# Arturo_Eagle_7_X.net
KiCad netlist of a schematic drawn in EAGLE
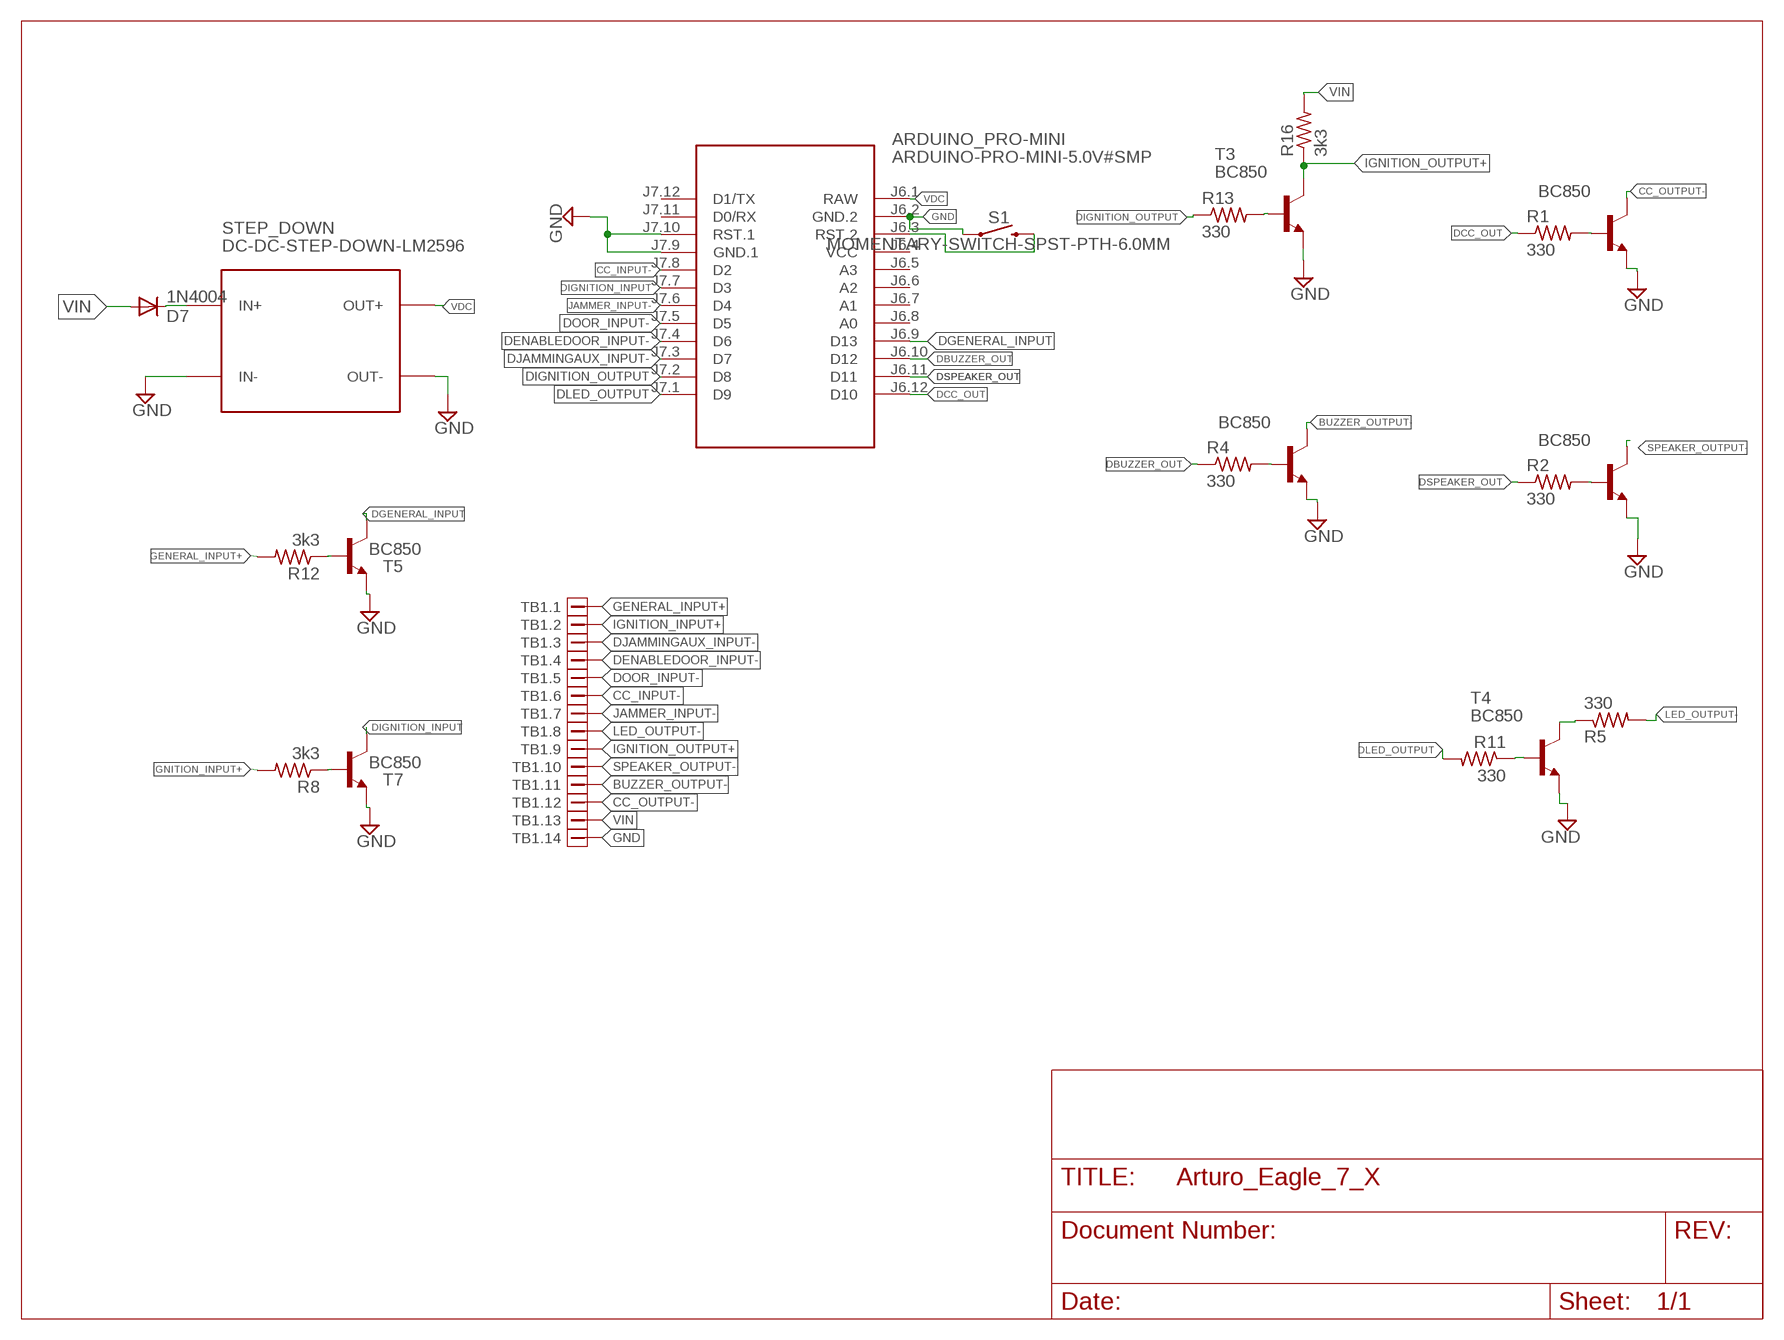
[diagram p0: schematic, sheet 1]

(export (version "E")
  (design (tool "Eeschema 10.0.6"))
  (components
    (comp (ref "ARDUINO_PRO-MINI")
      (value "ARDUINO-PRO-MINI-5.0V#SMP")
      (footprint "eagle-import:ARDUINO-PRO-MINI#SMP")
      (libsource (lib "eagle-import") (part "ARDUINO-PRO-MINI-#SMP5.0V"))
    )
    (comp (ref "D7")
      (value "1N4004")
      (footprint "eagle-import:DO41-10")
      (libsource (lib "eagle-import") (part "1N4004"))
    )
    (comp (ref "R1")
      (value "330")
      (footprint "eagle-import:R0805")
      (libsource (lib "eagle-import") (part "R-US_R0805"))
    )
    (comp (ref "R2")
      (value "330")
      (footprint "eagle-import:R0805")
      (libsource (lib "eagle-import") (part "R-US_R0805"))
    )
    (comp (ref "R4")
      (value "330")
      (footprint "eagle-import:R0805")
      (libsource (lib "eagle-import") (part "R-US_R0805"))
    )
    (comp (ref "R5")
      (value "330")
      (footprint "eagle-import:R0805")
      (libsource (lib "eagle-import") (part "R-US_R0805"))
    )
    (comp (ref "R8")
      (value "3k3")
      (footprint "eagle-import:R0805")
      (libsource (lib "eagle-import") (part "R-US_R0805"))
    )
    (comp (ref "R11")
      (value "330")
      (footprint "eagle-import:R0805")
      (libsource (lib "eagle-import") (part "R-US_R0805"))
    )
    (comp (ref "R12")
      (value "3k3")
      (footprint "eagle-import:R0805")
      (libsource (lib "eagle-import") (part "R-US_R0805"))
    )
    (comp (ref "R13")
      (value "330")
      (footprint "eagle-import:R0805")
      (libsource (lib "eagle-import") (part "R-US_R0805"))
    )
    (comp (ref "R16")
      (value "3k3")
      (footprint "eagle-import:R0805")
      (libsource (lib "eagle-import") (part "R-US_R0805"))
    )
    (comp (ref "S1")
      (value "MOMENTARY-SWITCH-SPST-PTH-6.0MM")
      (footprint "eagle-import:TACTILE_SWITCH_PTH_6.0MM")
      (libsource (lib "eagle-import") (part "MOMENTARY-SWITCH-SPST-PTH-6.0MM"))
    )
    (comp (ref "STEP_DOWN")
      (value "DC-DC-STEP-DOWN-LM2596")
      (footprint "eagle-import:DC-DC-STEP-DOWN-LM2596")
      (libsource (lib "eagle-import") (part "DC-DC-STEP-DOWN-LM2596"))
    )
    (comp (ref "T1")
      (value "BC850")
      (footprint "eagle-import:SOT23")
      (libsource (lib "eagle-import") (part "BC850"))
    )
    (comp (ref "T3")
      (value "BC850")
      (footprint "eagle-import:SOT23")
      (libsource (lib "eagle-import") (part "BC850"))
    )
    (comp (ref "T4")
      (value "BC850")
      (footprint "eagle-import:SOT23")
      (libsource (lib "eagle-import") (part "BC850"))
    )
    (comp (ref "T5")
      (value "BC850")
      (footprint "eagle-import:SOT23")
      (libsource (lib "eagle-import") (part "BC850"))
    )
    (comp (ref "T6")
      (value "BC850")
      (footprint "eagle-import:SOT23")
      (libsource (lib "eagle-import") (part "BC850"))
    )
    (comp (ref "T7")
      (value "BC850")
      (footprint "eagle-import:SOT23")
      (libsource (lib "eagle-import") (part "BC850"))
    )
    (comp (ref "T8")
      (value "BC850")
      (footprint "eagle-import:SOT23")
      (libsource (lib "eagle-import") (part "BC850"))
    )
    (comp (ref "TB1")
      (value "TB_PHOENIX")
      (footprint "eagle-import:TERMINAL_BLOCK_14POS")
      (libsource (lib "eagle-import") (part "TB_PHOENIX"))
    )
  )
  (nets
    (net (code "1") (name "/VCC") (class "Default")
      (node (ref "ARDUINO_PRO-MINI") (pin "J6.4") (pinfunction "VCC_J6.4") (pintype "power_in"))
    )
    (net (code "2") (name "BUZZER_OUTPUT-") (class "Default")
      (node (ref "T6") (pin "3") (pinfunction "C_3") (pintype "passive"))
      (node (ref "TB1") (pin "11") (pinfunction "1_11") (pintype "passive"))
      (node (ref "TB1") (pin "25") (pinfunction "1_25") (pintype "passive"))
    )
    (net (code "3") (name "CC_INPUT-") (class "Default")
      (node (ref "ARDUINO_PRO-MINI") (pin "J7.8") (pinfunction "D2_J7.8") (pintype "bidirectional"))
      (node (ref "TB1") (pin "20") (pinfunction "1_20") (pintype "passive"))
      (node (ref "TB1") (pin "6") (pinfunction "1_6") (pintype "passive"))
    )
    (net (code "4") (name "CC_OUTPUT-") (class "Default")
      (node (ref "T8") (pin "3") (pinfunction "C_3") (pintype "passive"))
      (node (ref "TB1") (pin "12") (pinfunction "1_12") (pintype "passive"))
      (node (ref "TB1") (pin "26") (pinfunction "1_26") (pintype "passive"))
    )
    (net (code "5") (name "DBUZZER_OUT") (class "Default")
      (node (ref "ARDUINO_PRO-MINI") (pin "J6.10") (pinfunction "D12_J6.10") (pintype "bidirectional"))
      (node (ref "R4") (pin "1") (pinfunction "1_1") (pintype "passive"))
    )
    (net (code "6") (name "DCC_OUT") (class "Default")
      (node (ref "ARDUINO_PRO-MINI") (pin "J6.12") (pinfunction "D10_J6.12") (pintype "bidirectional"))
      (node (ref "R1") (pin "1") (pinfunction "1_1") (pintype "passive"))
    )
    (net (code "7") (name "DENABLEDOOR_INPUT-") (class "Default")
      (node (ref "ARDUINO_PRO-MINI") (pin "J7.4") (pinfunction "D6_J7.4") (pintype "bidirectional"))
      (node (ref "TB1") (pin "18") (pinfunction "1_18") (pintype "passive"))
      (node (ref "TB1") (pin "4") (pinfunction "1_4") (pintype "passive"))
    )
    (net (code "8") (name "DGENERAL_INPUT") (class "Default")
      (node (ref "ARDUINO_PRO-MINI") (pin "J6.9") (pinfunction "D13_J6.9") (pintype "bidirectional"))
      (node (ref "T5") (pin "3") (pinfunction "C_3") (pintype "passive"))
    )
    (net (code "9") (name "DIGNITION_INPUT") (class "Default")
      (node (ref "ARDUINO_PRO-MINI") (pin "J7.7") (pinfunction "D3_J7.7") (pintype "bidirectional"))
      (node (ref "T7") (pin "3") (pinfunction "C_3") (pintype "passive"))
    )
    (net (code "10") (name "DIGNITION_OUTPUT") (class "Default")
      (node (ref "ARDUINO_PRO-MINI") (pin "J7.2") (pinfunction "D8_J7.2") (pintype "bidirectional"))
      (node (ref "R13") (pin "1") (pinfunction "1_1") (pintype "passive"))
    )
    (net (code "11") (name "DJAMMINGAUX_INPUT-") (class "Default")
      (node (ref "ARDUINO_PRO-MINI") (pin "J7.3") (pinfunction "D7_J7.3") (pintype "bidirectional"))
      (node (ref "TB1") (pin "17") (pinfunction "1_17") (pintype "passive"))
      (node (ref "TB1") (pin "3") (pinfunction "1_3") (pintype "passive"))
    )
    (net (code "12") (name "DLED_OUTPUT") (class "Default")
      (node (ref "ARDUINO_PRO-MINI") (pin "J7.1") (pinfunction "D9_J7.1") (pintype "bidirectional"))
      (node (ref "R11") (pin "2") (pinfunction "2_2") (pintype "passive"))
    )
    (net (code "13") (name "DOOR_INPUT-") (class "Default")
      (node (ref "ARDUINO_PRO-MINI") (pin "J7.5") (pinfunction "D5_J7.5") (pintype "bidirectional"))
      (node (ref "TB1") (pin "19") (pinfunction "1_19") (pintype "passive"))
      (node (ref "TB1") (pin "5") (pinfunction "1_5") (pintype "passive"))
    )
    (net (code "14") (name "DSPEAKER_OUT") (class "Default")
      (node (ref "ARDUINO_PRO-MINI") (pin "J6.11") (pinfunction "D11_J6.11") (pintype "bidirectional"))
      (node (ref "R2") (pin "1") (pinfunction "1_1") (pintype "passive"))
    )
    (net (code "15") (name "GENERAL_INPUT+") (class "Default")
      (node (ref "R12") (pin "2") (pinfunction "2_2") (pintype "passive"))
      (node (ref "TB1") (pin "1") (pinfunction "1_1") (pintype "passive"))
      (node (ref "TB1") (pin "15") (pinfunction "1_15") (pintype "passive"))
    )
    (net (code "16") (name "GND") (class "Default")
      (node (ref "ARDUINO_PRO-MINI") (pin "J6.2") (pinfunction "GND.2_J6.2") (pintype "power_in"))
      (node (ref "ARDUINO_PRO-MINI") (pin "J7.10") (pinfunction "RST.1_J7.10") (pintype "bidirectional"))
      (node (ref "ARDUINO_PRO-MINI") (pin "J7.9") (pinfunction "GND.1_J7.9") (pintype "power_in"))
      (node (ref "S1") (pin "1") (pinfunction "1_1") (pintype "passive"))
      (node (ref "STEP_DOWN") (pin "IN-") (pinfunction "IN-_IN-") (pintype "bidirectional"))
      (node (ref "STEP_DOWN") (pin "OUT-") (pinfunction "OUT-_OUT-") (pintype "bidirectional"))
      (node (ref "T1") (pin "2") (pinfunction "E_2") (pintype "passive"))
      (node (ref "T3") (pin "2") (pinfunction "E_2") (pintype "passive"))
      (node (ref "T4") (pin "2") (pinfunction "E_2") (pintype "passive"))
      (node (ref "T5") (pin "2") (pinfunction "E_2") (pintype "passive"))
      (node (ref "T6") (pin "2") (pinfunction "E_2") (pintype "passive"))
      (node (ref "T7") (pin "2") (pinfunction "E_2") (pintype "passive"))
      (node (ref "T8") (pin "2") (pinfunction "E_2") (pintype "passive"))
      (node (ref "TB1") (pin "14") (pinfunction "1_14") (pintype "passive"))
      (node (ref "TB1") (pin "28") (pinfunction "1_28") (pintype "passive"))
    )
    (net (code "17") (name "IGNITION_INPUT+") (class "Default")
      (node (ref "R8") (pin "2") (pinfunction "2_2") (pintype "passive"))
      (node (ref "TB1") (pin "16") (pinfunction "1_16") (pintype "passive"))
      (node (ref "TB1") (pin "2") (pinfunction "1_2") (pintype "passive"))
    )
    (net (code "18") (name "IGNITION_OUTPUT+") (class "Default")
      (node (ref "R16") (pin "1") (pinfunction "1_1") (pintype "passive"))
      (node (ref "T3") (pin "3") (pinfunction "C_3") (pintype "passive"))
      (node (ref "TB1") (pin "23") (pinfunction "1_23") (pintype "passive"))
      (node (ref "TB1") (pin "9") (pinfunction "1_9") (pintype "passive"))
    )
    (net (code "19") (name "JAMMER_INPUT-") (class "Default")
      (node (ref "ARDUINO_PRO-MINI") (pin "J7.6") (pinfunction "D4_J7.6") (pintype "bidirectional"))
      (node (ref "TB1") (pin "21") (pinfunction "1_21") (pintype "passive"))
      (node (ref "TB1") (pin "7") (pinfunction "1_7") (pintype "passive"))
    )
    (net (code "20") (name "LED_OUTPUT-") (class "Default")
      (node (ref "R5") (pin "2") (pinfunction "2_2") (pintype "passive"))
      (node (ref "TB1") (pin "22") (pinfunction "1_22") (pintype "passive"))
      (node (ref "TB1") (pin "8") (pinfunction "1_8") (pintype "passive"))
    )
    (net (code "21") (name "Net-(ARDUINO_PRO-MINI-RST.2)") (class "Default")
      (node (ref "ARDUINO_PRO-MINI") (pin "J6.3") (pinfunction "RST.2_J6.3") (pintype "bidirectional"))
      (node (ref "S1") (pin "3") (pinfunction "2_3") (pintype "passive"))
    )
    (net (code "22") (name "Net-(D7-PadC)") (class "Default")
      (node (ref "D7") (pin "C") (pinfunction "C_C") (pintype "passive"))
      (node (ref "STEP_DOWN") (pin "IN+") (pinfunction "IN+_IN+") (pintype "bidirectional"))
    )
    (net (code "23") (name "Net-(T1-B)") (class "Default")
      (node (ref "R2") (pin "2") (pinfunction "2_2") (pintype "passive"))
      (node (ref "T1") (pin "1") (pinfunction "B_1") (pintype "passive"))
    )
    (net (code "24") (name "Net-(T3-B)") (class "Default")
      (node (ref "R13") (pin "2") (pinfunction "2_2") (pintype "passive"))
      (node (ref "T3") (pin "1") (pinfunction "B_1") (pintype "passive"))
    )
    (net (code "25") (name "Net-(T4-B)") (class "Default")
      (node (ref "R11") (pin "1") (pinfunction "1_1") (pintype "passive"))
      (node (ref "T4") (pin "1") (pinfunction "B_1") (pintype "passive"))
    )
    (net (code "26") (name "Net-(T4-C)") (class "Default")
      (node (ref "R5") (pin "1") (pinfunction "1_1") (pintype "passive"))
      (node (ref "T4") (pin "3") (pinfunction "C_3") (pintype "passive"))
    )
    (net (code "27") (name "Net-(T5-B)") (class "Default")
      (node (ref "R12") (pin "1") (pinfunction "1_1") (pintype "passive"))
      (node (ref "T5") (pin "1") (pinfunction "B_1") (pintype "passive"))
    )
    (net (code "28") (name "Net-(T6-B)") (class "Default")
      (node (ref "R4") (pin "2") (pinfunction "2_2") (pintype "passive"))
      (node (ref "T6") (pin "1") (pinfunction "B_1") (pintype "passive"))
    )
    (net (code "29") (name "Net-(T7-B)") (class "Default")
      (node (ref "R8") (pin "1") (pinfunction "1_1") (pintype "passive"))
      (node (ref "T7") (pin "1") (pinfunction "B_1") (pintype "passive"))
    )
    (net (code "30") (name "Net-(T8-B)") (class "Default")
      (node (ref "R1") (pin "2") (pinfunction "2_2") (pintype "passive"))
      (node (ref "T8") (pin "1") (pinfunction "B_1") (pintype "passive"))
    )
    (net (code "31") (name "SPEAKER_OUTPUT-") (class "Default")
      (node (ref "T1") (pin "3") (pinfunction "C_3") (pintype "passive"))
      (node (ref "TB1") (pin "10") (pinfunction "1_10") (pintype "passive"))
      (node (ref "TB1") (pin "24") (pinfunction "1_24") (pintype "passive"))
    )
    (net (code "32") (name "VDC") (class "Default")
      (node (ref "ARDUINO_PRO-MINI") (pin "J6.1") (pinfunction "RAW_J6.1") (pintype "power_in"))
      (node (ref "STEP_DOWN") (pin "OUT+") (pinfunction "OUT+_OUT+") (pintype "bidirectional"))
    )
    (net (code "33") (name "VIN") (class "Default")
      (node (ref "D7") (pin "A") (pinfunction "A_A") (pintype "passive"))
      (node (ref "R16") (pin "2") (pinfunction "2_2") (pintype "passive"))
      (node (ref "TB1") (pin "13") (pinfunction "1_13") (pintype "passive"))
      (node (ref "TB1") (pin "27") (pinfunction "1_27") (pintype "passive"))
    )
    (net (code "34") (name "unconnected-(ARDUINO_PRO-MINI-A0-PadJ6.8)") (class "Default")
      (node (ref "ARDUINO_PRO-MINI") (pin "J6.8") (pinfunction "A0_J6.8") (pintype "bidirectional"))
    )
    (net (code "35") (name "unconnected-(ARDUINO_PRO-MINI-A1-PadJ6.7)") (class "Default")
      (node (ref "ARDUINO_PRO-MINI") (pin "J6.7") (pinfunction "A1_J6.7") (pintype "bidirectional"))
    )
    (net (code "36") (name "unconnected-(ARDUINO_PRO-MINI-A2-PadJ6.6)") (class "Default")
      (node (ref "ARDUINO_PRO-MINI") (pin "J6.6") (pinfunction "A2_J6.6") (pintype "bidirectional"))
    )
    (net (code "37") (name "unconnected-(ARDUINO_PRO-MINI-A3-PadJ6.5)") (class "Default")
      (node (ref "ARDUINO_PRO-MINI") (pin "J6.5") (pinfunction "A3_J6.5") (pintype "bidirectional"))
    )
    (net (code "38") (name "unconnected-(ARDUINO_PRO-MINI-D0{slash}RX-PadJ7.11)") (class "Default")
      (node (ref "ARDUINO_PRO-MINI") (pin "J7.11") (pinfunction "D0/RX_J7.11") (pintype "bidirectional"))
    )
    (net (code "39") (name "unconnected-(ARDUINO_PRO-MINI-D1{slash}TX-PadJ7.12)") (class "Default")
      (node (ref "ARDUINO_PRO-MINI") (pin "J7.12") (pinfunction "D1/TX_J7.12") (pintype "bidirectional"))
    )
  )
)
